# Pas_Schematic.net
KiCad netlist of a schematic drawn in Altium Designer
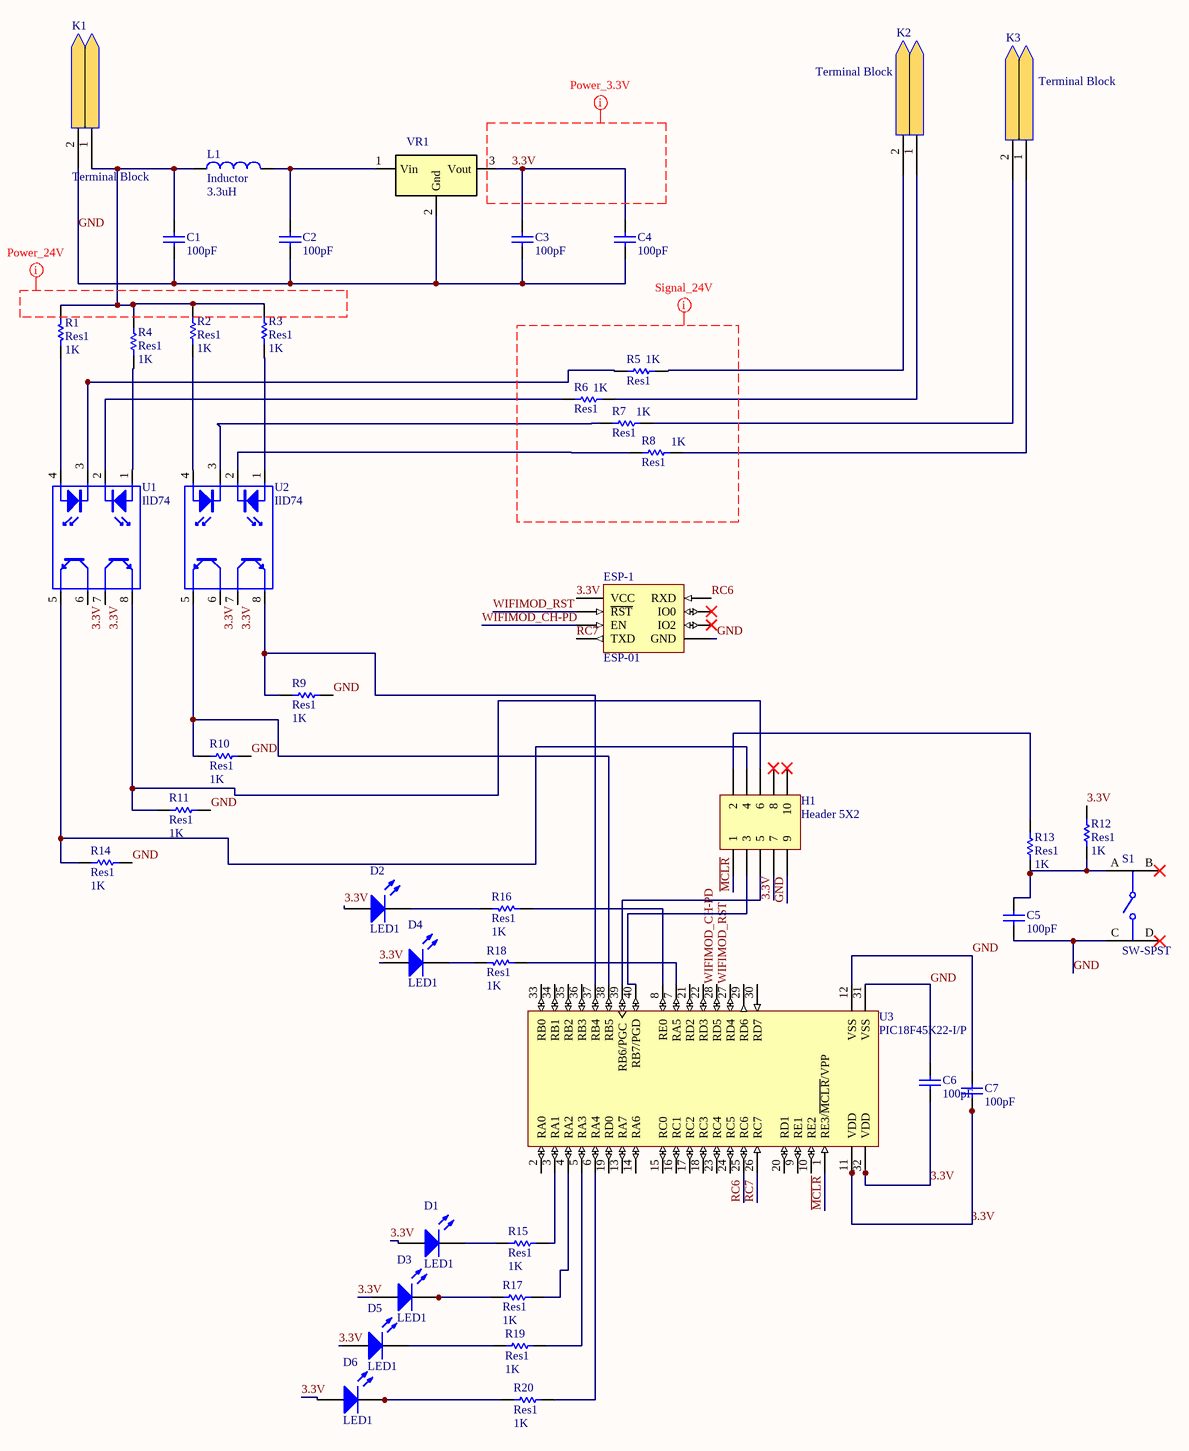
[diagram p0: Pas_Schematic.SchDoc]

(export (version "E")
  (design (tool "Eeschema 10.0.6"))
  (components
    (comp (ref "C1")
      (value "100pF")
      (footprint "RADIAL_0.2")
      (description "Capacitor")
      (fields (field (name "PUBLISHER") "Altium Limited"))
      (libsource (lib "Patient Alarm System Altium Integrated Library of Components") (part "Capacitor"))
    )
    (comp (ref "C2")
      (value "100pF")
      (footprint "RADIAL_0.2")
      (description "Capacitor")
      (fields (field (name "PUBLISHER") "Altium Limited"))
      (libsource (lib "Patient Alarm System Altium Integrated Library of Components") (part "Capacitor"))
    )
    (comp (ref "C3")
      (value "100pF")
      (footprint "RADIAL_0.2")
      (description "Capacitor")
      (fields (field (name "PUBLISHER") "Altium Limited"))
      (libsource (lib "Patient Alarm System Altium Integrated Library of Components") (part "Capacitor"))
    )
    (comp (ref "C4")
      (value "100pF")
      (footprint "RADIAL_0.2")
      (description "Capacitor")
      (fields (field (name "PUBLISHER") "Altium Limited"))
      (libsource (lib "Patient Alarm System Altium Integrated Library of Components") (part "Capacitor"))
    )
    (comp (ref "C5")
      (value "100pF")
      (footprint "RADIAL_0.2")
      (description "Capacitor")
      (fields (field (name "PUBLISHER") "Altium Limited"))
      (libsource (lib "Patient Alarm System Altium Integrated Library of Components") (part "Capacitor"))
    )
    (comp (ref "C6")
      (value "100pF")
      (footprint "RADIAL_0.2")
      (description "Capacitor")
      (fields (field (name "PUBLISHER") "Altium Limited"))
      (libsource (lib "Patient Alarm System Altium Integrated Library of Components") (part "Capacitor"))
    )
    (comp (ref "C7")
      (value "100pF")
      (footprint "RADIAL_0.2")
      (description "Capacitor")
      (fields (field (name "PUBLISHER") "Altium Limited"))
      (libsource (lib "Patient Alarm System Altium Integrated Library of Components") (part "Capacitor"))
    )
    (comp (ref "D1")
      (value "LED1")
      (footprint "RADIAL_0.2")
      (description "Typical RED GaAs LED")
      (fields (field (name "PUBLISHER") "Altium Limited"))
      (libsource (lib "Patient Alarm System Altium Integrated Library of Components") (part "LED1"))
    )
    (comp (ref "D2")
      (value "LED1")
      (footprint "RADIAL_0.2")
      (description "Typical RED GaAs LED")
      (fields (field (name "PUBLISHER") "Altium Limited"))
      (libsource (lib "Patient Alarm System Altium Integrated Library of Components") (part "LED1"))
    )
    (comp (ref "D3")
      (value "LED1")
      (footprint "RADIAL_0.2")
      (description "Typical RED GaAs LED")
      (fields (field (name "PUBLISHER") "Altium Limited"))
      (libsource (lib "Patient Alarm System Altium Integrated Library of Components") (part "LED1"))
    )
    (comp (ref "D4")
      (value "LED1")
      (footprint "RADIAL_0.2")
      (description "Typical RED GaAs LED")
      (fields (field (name "PUBLISHER") "Altium Limited"))
      (libsource (lib "Patient Alarm System Altium Integrated Library of Components") (part "LED1"))
    )
    (comp (ref "D5")
      (value "LED1")
      (footprint "RADIAL_0.2")
      (description "Typical RED GaAs LED")
      (fields (field (name "PUBLISHER") "Altium Limited"))
      (libsource (lib "Patient Alarm System Altium Integrated Library of Components") (part "LED1"))
    )
    (comp (ref "D6")
      (value "LED1")
      (footprint "RADIAL_0.2")
      (description "Typical RED GaAs LED")
      (fields (field (name "PUBLISHER") "Altium Limited"))
      (libsource (lib "Patient Alarm System Altium Integrated Library of Components") (part "LED1"))
    )
    (comp (ref "ESP-1")
      (value "ESP-01")
      (footprint "ESP-01")
      (description "802.11b/g/n Wi-Fi SOC module")
      (fields (field (name "PUBLISHER") "Altium Limited"))
      (libsource (lib "Patient Alarm System Altium Integrated Library of Components") (part "ESP-01"))
    )
    (comp (ref "H1")
      (value "Header 5X2")
      (footprint "HDR2X5")
      (description "Header, 5-Pin, Dual row")
      (fields (field (name "PUBLISHER") "Altium Limited"))
      (libsource (lib "Miscellaneous Connectors") (part "Header 5X2"))
    )
    (comp (ref "K1")
      (value "Terminal Block")
      (footprint "Altech MV-252")
      (libsource (lib "Schematic Components") (part "Terminal Block"))
    )
    (comp (ref "K2")
      (value "Terminal Block")
      (footprint "Altech MV-252")
      (libsource (lib "Schematic Components") (part "Terminal Block"))
    )
    (comp (ref "K3")
      (value "Terminal Block")
      (footprint "Altech MV-252")
      (libsource (lib "Schematic Components") (part "Terminal Block"))
    )
    (comp (ref "L1")
      (value "Inductor")
      (footprint "RADIAL_3.5")
      (fields (field (name "ALTIUM_VALUE") "3.3uH") (field (name "PUBLISHER") "Altium Limited"))
      (libsource (lib "Patient Alarm System Altium Integrated Library of Components") (part "Inductor"))
    )
    (comp (ref "R1")
      (value "Res1")
      (footprint "AXIAL-0.3")
      (description "Resistor")
      (fields (field (name "ALTIUM_VALUE") "1K") (field (name "PUBLISHER") "Altium Limited"))
      (libsource (lib "Patient Alarm System Altium Integrated Library of Components") (part "Res1"))
    )
    (comp (ref "R2")
      (value "Res1")
      (footprint "AXIAL-0.3")
      (description "Resistor")
      (fields (field (name "ALTIUM_VALUE") "1K") (field (name "PUBLISHER") "Altium Limited"))
      (libsource (lib "Patient Alarm System Altium Integrated Library of Components") (part "Res1"))
    )
    (comp (ref "R3")
      (value "Res1")
      (footprint "AXIAL-0.3")
      (description "Resistor")
      (fields (field (name "ALTIUM_VALUE") "1K") (field (name "PUBLISHER") "Altium Limited"))
      (libsource (lib "Patient Alarm System Altium Integrated Library of Components") (part "Res1"))
    )
    (comp (ref "R4")
      (value "Res1")
      (footprint "AXIAL-0.3")
      (description "Resistor")
      (fields (field (name "ALTIUM_VALUE") "1K") (field (name "PUBLISHER") "Altium Limited"))
      (libsource (lib "Patient Alarm System Altium Integrated Library of Components") (part "Res1"))
    )
    (comp (ref "R5")
      (value "Res1")
      (footprint "AXIAL-0.3")
      (description "Resistor")
      (fields (field (name "ALTIUM_VALUE") "1K") (field (name "PUBLISHER") "Altium Limited"))
      (libsource (lib "Patient Alarm System Altium Integrated Library of Components") (part "Res1"))
    )
    (comp (ref "R6")
      (value "Res1")
      (footprint "AXIAL-0.3")
      (description "Resistor")
      (fields (field (name "ALTIUM_VALUE") "1K") (field (name "PUBLISHER") "Altium Limited"))
      (libsource (lib "Patient Alarm System Altium Integrated Library of Components") (part "Res1"))
    )
    (comp (ref "R7")
      (value "Res1")
      (footprint "AXIAL-0.3")
      (description "Resistor")
      (fields (field (name "ALTIUM_VALUE") "1K") (field (name "PUBLISHER") "Altium Limited"))
      (libsource (lib "Patient Alarm System Altium Integrated Library of Components") (part "Res1"))
    )
    (comp (ref "R8")
      (value "Res1")
      (footprint "AXIAL-0.3")
      (description "Resistor")
      (fields (field (name "ALTIUM_VALUE") "1K") (field (name "PUBLISHER") "Altium Limited"))
      (libsource (lib "Patient Alarm System Altium Integrated Library of Components") (part "Res1"))
    )
    (comp (ref "R9")
      (value "Res1")
      (footprint "AXIAL-0.3")
      (description "Resistor")
      (fields (field (name "ALTIUM_VALUE") "1K") (field (name "PUBLISHER") "Altium Limited"))
      (libsource (lib "Patient Alarm System Altium Integrated Library of Components") (part "Res1"))
    )
    (comp (ref "R10")
      (value "Res1")
      (footprint "AXIAL-0.3")
      (description "Resistor")
      (fields (field (name "ALTIUM_VALUE") "1K") (field (name "PUBLISHER") "Altium Limited"))
      (libsource (lib "Patient Alarm System Altium Integrated Library of Components") (part "Res1"))
    )
    (comp (ref "R11")
      (value "Res1")
      (footprint "AXIAL-0.3")
      (description "Resistor")
      (fields (field (name "ALTIUM_VALUE") "1K") (field (name "PUBLISHER") "Altium Limited"))
      (libsource (lib "Patient Alarm System Altium Integrated Library of Components") (part "Res1"))
    )
    (comp (ref "R12")
      (value "Res1")
      (footprint "AXIAL-0.3")
      (description "Resistor")
      (fields (field (name "ALTIUM_VALUE") "1K") (field (name "PUBLISHER") "Altium Limited"))
      (libsource (lib "Patient Alarm System Altium Integrated Library of Components") (part "Res1"))
    )
    (comp (ref "R13")
      (value "Res1")
      (footprint "AXIAL-0.3")
      (description "Resistor")
      (fields (field (name "ALTIUM_VALUE") "1K") (field (name "PUBLISHER") "Altium Limited"))
      (libsource (lib "Patient Alarm System Altium Integrated Library of Components") (part "Res1"))
    )
    (comp (ref "R14")
      (value "Res1")
      (footprint "AXIAL-0.3")
      (description "Resistor")
      (fields (field (name "ALTIUM_VALUE") "1K") (field (name "PUBLISHER") "Altium Limited"))
      (libsource (lib "Patient Alarm System Altium Integrated Library of Components") (part "Res1"))
    )
    (comp (ref "R15")
      (value "Res1")
      (footprint "AXIAL-0.3")
      (description "Resistor")
      (fields (field (name "ALTIUM_VALUE") "1K") (field (name "PUBLISHER") "Altium Limited"))
      (libsource (lib "Patient Alarm System Altium Integrated Library of Components") (part "Res1"))
    )
    (comp (ref "R16")
      (value "Res1")
      (footprint "AXIAL-0.3")
      (description "Resistor")
      (fields (field (name "ALTIUM_VALUE") "1K") (field (name "PUBLISHER") "Altium Limited"))
      (libsource (lib "Patient Alarm System Altium Integrated Library of Components") (part "Res1"))
    )
    (comp (ref "R17")
      (value "Res1")
      (footprint "AXIAL-0.3")
      (description "Resistor")
      (fields (field (name "ALTIUM_VALUE") "1K") (field (name "PUBLISHER") "Altium Limited"))
      (libsource (lib "Patient Alarm System Altium Integrated Library of Components") (part "Res1"))
    )
    (comp (ref "R18")
      (value "Res1")
      (footprint "AXIAL-0.3")
      (description "Resistor")
      (fields (field (name "ALTIUM_VALUE") "1K") (field (name "PUBLISHER") "Altium Limited"))
      (libsource (lib "Patient Alarm System Altium Integrated Library of Components") (part "Res1"))
    )
    (comp (ref "R19")
      (value "Res1")
      (footprint "AXIAL-0.3")
      (description "Resistor")
      (fields (field (name "ALTIUM_VALUE") "1K") (field (name "PUBLISHER") "Altium Limited"))
      (libsource (lib "Patient Alarm System Altium Integrated Library of Components") (part "Res1"))
    )
    (comp (ref "R20")
      (value "Res1")
      (footprint "AXIAL-0.3")
      (description "Resistor")
      (fields (field (name "ALTIUM_VALUE") "1K") (field (name "PUBLISHER") "Altium Limited"))
      (libsource (lib "Patient Alarm System Altium Integrated Library of Components") (part "Res1"))
    )
    (comp (ref "S1")
      (value "SW-SPST")
      (footprint "SW-SPST-1")
      (description "4-pin Single-Pole, Single-Throw Switch")
      (fields (field (name "PUBLISHER") "Altium Limited"))
      (libsource (lib "Patient Alarm System Altium Integrated Library of Components") (part "SW-SPST"))
    )
    (comp (ref "U1")
      (value "IlD74")
      (footprint "DIP-8")
      (description "8-pin Dual Optocoupler with NPN Transistor Output")
      (fields (field (name "PUBLISHER") "Altium Limited"))
      (libsource (lib "Patient Alarm System Altium Integrated Library of Components") (part "IlD74"))
    )
    (comp (ref "U2")
      (value "IlD74")
      (footprint "DIP-8")
      (description "8-pin Dual Optocoupler with NPN Transistor Output")
      (fields (field (name "PUBLISHER") "Altium Limited"))
      (libsource (lib "Patient Alarm System Altium Integrated Library of Components") (part "IlD74"))
    )
    (comp (ref "U3")
      (value "PIC18F45K22-I/P")
      (footprint "MCHP-PDIP-P40")
      (fields (field (name "MANUFACTURER") "Microchip"))
      (libsource (lib "Patient Alarm System Altium Integrated Library of Components") (part "PIC18F45K22-I/P"))
    )
    (comp (ref "VR1")
      (value "REG")
      (footprint "SIP3")
      (description "Non-Isolated DC/DC Converters 0.5A DC/DC REG 4.75-34Vin 3.3Vout")
      (libsource (lib "Patient Alarm System Altium Integrated Library of Components") (part "R-783.3-0.5"))
    )
  )
  (nets
    (net (code "1") (name "/3.3V") (class "Default")
      (node (ref "C3") (pin "1") (pinfunction "1_1") (pintype "passive"))
      (node (ref "C4") (pin "1") (pinfunction "1_1") (pintype "passive"))
      (node (ref "C6") (pin "1") (pinfunction "1_1") (pintype "passive"))
      (node (ref "C7") (pin "1") (pinfunction "1_1") (pintype "passive"))
      (node (ref "D1") (pin "1") (pinfunction "A_1") (pintype "passive"))
      (node (ref "D2") (pin "1") (pinfunction "A_1") (pintype "passive"))
      (node (ref "D3") (pin "1") (pinfunction "A_1") (pintype "passive"))
      (node (ref "D4") (pin "1") (pinfunction "A_1") (pintype "passive"))
      (node (ref "D5") (pin "1") (pinfunction "A_1") (pintype "passive"))
      (node (ref "D6") (pin "1") (pinfunction "A_1") (pintype "passive"))
      (node (ref "ESP-1") (pin "8") (pinfunction "VCC_8") (pintype "power_in"))
      (node (ref "H1") (pin "7") (pinfunction "7_7") (pintype "passive"))
      (node (ref "R12") (pin "2") (pinfunction "2_2") (pintype "passive"))
      (node (ref "U1") (pin "6") (pinfunction "C_6") (pintype "passive"))
      (node (ref "U1") (pin "7") (pinfunction "C_7") (pintype "passive"))
      (node (ref "U2") (pin "6") (pinfunction "C_6") (pintype "passive"))
      (node (ref "U2") (pin "7") (pinfunction "C_7") (pintype "passive"))
      (node (ref "U3") (pin "11") (pinfunction "VDD_11") (pintype "power_in"))
      (node (ref "U3") (pin "32") (pinfunction "VDD_32") (pintype "power_in"))
      (node (ref "VR1") (pin "3") (pinfunction "Vout_3") (pintype "power_in"))
    )
    (net (code "2") (name "/GND") (class "Default")
      (node (ref "C1") (pin "2") (pinfunction "2_2") (pintype "passive"))
      (node (ref "C2") (pin "2") (pinfunction "2_2") (pintype "passive"))
      (node (ref "C3") (pin "2") (pinfunction "2_2") (pintype "passive"))
      (node (ref "C4") (pin "2") (pinfunction "2_2") (pintype "passive"))
      (node (ref "C5") (pin "2") (pinfunction "2_2") (pintype "passive"))
      (node (ref "C6") (pin "2") (pinfunction "2_2") (pintype "passive"))
      (node (ref "C7") (pin "2") (pinfunction "2_2") (pintype "passive"))
      (node (ref "ESP-1") (pin "1") (pinfunction "GND_1") (pintype "power_in"))
      (node (ref "H1") (pin "9") (pinfunction "9_9") (pintype "passive"))
      (node (ref "K1") (pin "2") (pinfunction "Cable_2_2") (pintype "passive"))
      (node (ref "R10") (pin "1") (pinfunction "1_1") (pintype "passive"))
      (node (ref "R11") (pin "1") (pinfunction "1_1") (pintype "passive"))
      (node (ref "R14") (pin "1") (pinfunction "1_1") (pintype "passive"))
      (node (ref "R9") (pin "1") (pinfunction "1_1") (pintype "passive"))
      (node (ref "S1") (pin "C") (pinfunction "NO_C") (pintype "passive"))
      (node (ref "U3") (pin "12") (pinfunction "VSS_12") (pintype "power_in"))
      (node (ref "U3") (pin "31") (pinfunction "VSS_31") (pintype "power_in"))
      (node (ref "VR1") (pin "2") (pinfunction "Gnd_2") (pintype "power_in"))
    )
    (net (code "3") (name "/RC6") (class "Default")
      (node (ref "ESP-1") (pin "4") (pinfunction "RXD_4") (pintype "input"))
      (node (ref "U3") (pin "25") (pinfunction "RC6_25") (pintype "bidirectional"))
    )
    (net (code "4") (name "/RC7") (class "Default")
      (node (ref "ESP-1") (pin "5") (pinfunction "TXD_5") (pintype "output"))
      (node (ref "U3") (pin "26") (pinfunction "RC7_26") (pintype "input"))
    )
    (net (code "5") (name "/WIFIMOD_CH-PD") (class "Default")
      (node (ref "ESP-1") (pin "6") (pinfunction "EN_6") (pintype "input"))
      (node (ref "U3") (pin "28") (pinfunction "RD5_28") (pintype "bidirectional"))
    )
    (net (code "6") (name "/WIFIMOD_RST") (class "Default")
      (node (ref "ESP-1") (pin "7") (pinfunction "~{RST}_7") (pintype "input"))
      (node (ref "U3") (pin "27") (pinfunction "RD4_27") (pintype "bidirectional"))
    )
    (net (code "7") (name "/~{MCLR}") (class "Default")
      (node (ref "H1") (pin "1") (pinfunction "1_1") (pintype "power_in"))
      (node (ref "U3") (pin "1") (pinfunction "RE3/~{MCLR}/VPP_1") (pintype "input"))
    )
    (net (code "8") (name "Net-(C5-Pad1)") (class "Default")
      (node (ref "C5") (pin "1") (pinfunction "1_1") (pintype "passive"))
      (node (ref "R12") (pin "1") (pinfunction "1_1") (pintype "passive"))
      (node (ref "R13") (pin "1") (pinfunction "1_1") (pintype "passive"))
      (node (ref "S1") (pin "A") (pinfunction "COMMON_A") (pintype "passive"))
    )
    (net (code "9") (name "Net-(D1-K)") (class "Default")
      (node (ref "D1") (pin "2") (pinfunction "K_2") (pintype "passive"))
      (node (ref "R15") (pin "2") (pinfunction "2_2") (pintype "passive"))
    )
    (net (code "10") (name "Net-(D2-K)") (class "Default")
      (node (ref "D2") (pin "2") (pinfunction "K_2") (pintype "passive"))
      (node (ref "R16") (pin "2") (pinfunction "2_2") (pintype "passive"))
    )
    (net (code "11") (name "Net-(D3-K)") (class "Default")
      (node (ref "D3") (pin "2") (pinfunction "K_2") (pintype "passive"))
      (node (ref "R17") (pin "1") (pinfunction "1_1") (pintype "passive"))
    )
    (net (code "12") (name "Net-(D4-K)") (class "Default")
      (node (ref "D4") (pin "2") (pinfunction "K_2") (pintype "passive"))
      (node (ref "R18") (pin "2") (pinfunction "2_2") (pintype "passive"))
    )
    (net (code "13") (name "Net-(D5-K)") (class "Default")
      (node (ref "D5") (pin "2") (pinfunction "K_2") (pintype "passive"))
      (node (ref "R19") (pin "1") (pinfunction "1_1") (pintype "passive"))
    )
    (net (code "14") (name "Net-(D6-K)") (class "Default")
      (node (ref "D6") (pin "2") (pinfunction "K_2") (pintype "passive"))
      (node (ref "R20") (pin "1") (pinfunction "1_1") (pintype "passive"))
    )
    (net (code "15") (name "Net-(H1-Pad2)") (class "Default")
      (node (ref "H1") (pin "2") (pinfunction "2_2") (pintype "passive"))
      (node (ref "R13") (pin "2") (pinfunction "2_2") (pintype "passive"))
    )
    (net (code "16") (name "Net-(H1-Pad4)") (class "Default")
      (node (ref "H1") (pin "4") (pinfunction "4_4") (pintype "passive"))
      (node (ref "R14") (pin "2") (pinfunction "2_2") (pintype "passive"))
      (node (ref "U1") (pin "5") (pinfunction "E_5") (pintype "passive"))
    )
    (net (code "17") (name "Net-(H1-Pad6)") (class "Default")
      (node (ref "H1") (pin "6") (pinfunction "6_6") (pintype "passive"))
      (node (ref "R11") (pin "2") (pinfunction "2_2") (pintype "passive"))
      (node (ref "U1") (pin "8") (pinfunction "E_8") (pintype "passive"))
    )
    (net (code "18") (name "Net-(K1-Cable_1)") (class "Default")
      (node (ref "C1") (pin "1") (pinfunction "1_1") (pintype "passive"))
      (node (ref "K1") (pin "1") (pinfunction "Cable_1_1") (pintype "passive"))
      (node (ref "L1") (pin "1") (pinfunction "1_1") (pintype "passive"))
      (node (ref "R1") (pin "1") (pinfunction "1_1") (pintype "passive"))
      (node (ref "R2") (pin "2") (pinfunction "2_2") (pintype "passive"))
      (node (ref "R3") (pin "2") (pinfunction "2_2") (pintype "passive"))
      (node (ref "R4") (pin "2") (pinfunction "2_2") (pintype "passive"))
    )
    (net (code "19") (name "Net-(K2-Cable_1)") (class "Default")
      (node (ref "K2") (pin "1") (pinfunction "Cable_1_1") (pintype "passive"))
      (node (ref "R6") (pin "2") (pinfunction "2_2") (pintype "passive"))
    )
    (net (code "20") (name "Net-(K2-Cable_2)") (class "Default")
      (node (ref "K2") (pin "2") (pinfunction "Cable_2_2") (pintype "passive"))
      (node (ref "R5") (pin "2") (pinfunction "2_2") (pintype "passive"))
    )
    (net (code "21") (name "Net-(K3-Cable_1)") (class "Default")
      (node (ref "K3") (pin "1") (pinfunction "Cable_1_1") (pintype "passive"))
      (node (ref "R8") (pin "2") (pinfunction "2_2") (pintype "passive"))
    )
    (net (code "22") (name "Net-(K3-Cable_2)") (class "Default")
      (node (ref "K3") (pin "2") (pinfunction "Cable_2_2") (pintype "passive"))
      (node (ref "R7") (pin "2") (pinfunction "2_2") (pintype "passive"))
    )
    (net (code "23") (name "Net-(R1-Pad2)") (class "Default")
      (node (ref "R1") (pin "2") (pinfunction "2_2") (pintype "passive"))
      (node (ref "U1") (pin "4") (pinfunction "A_4") (pintype "passive"))
    )
    (net (code "24") (name "Net-(R2-Pad1)") (class "Default")
      (node (ref "R2") (pin "1") (pinfunction "1_1") (pintype "passive"))
      (node (ref "U2") (pin "4") (pinfunction "A_4") (pintype "passive"))
    )
    (net (code "25") (name "Net-(R3-Pad1)") (class "Default")
      (node (ref "R3") (pin "1") (pinfunction "1_1") (pintype "passive"))
      (node (ref "U2") (pin "1") (pinfunction "A_1") (pintype "passive"))
    )
    (net (code "26") (name "Net-(R4-Pad1)") (class "Default")
      (node (ref "R4") (pin "1") (pinfunction "1_1") (pintype "passive"))
      (node (ref "U1") (pin "1") (pinfunction "A_1") (pintype "passive"))
    )
    (net (code "27") (name "Net-(R5-Pad1)") (class "Default")
      (node (ref "R5") (pin "1") (pinfunction "1_1") (pintype "passive"))
      (node (ref "U1") (pin "3") (pinfunction "K_3") (pintype "passive"))
    )
    (net (code "28") (name "Net-(R6-Pad1)") (class "Default")
      (node (ref "R6") (pin "1") (pinfunction "1_1") (pintype "passive"))
      (node (ref "U1") (pin "2") (pinfunction "K_2") (pintype "passive"))
    )
    (net (code "29") (name "Net-(R7-Pad1)") (class "Default")
      (node (ref "R7") (pin "1") (pinfunction "1_1") (pintype "passive"))
      (node (ref "U2") (pin "3") (pinfunction "K_3") (pintype "passive"))
    )
    (net (code "30") (name "Net-(R8-Pad1)") (class "Default")
      (node (ref "R8") (pin "1") (pinfunction "1_1") (pintype "passive"))
      (node (ref "U2") (pin "2") (pinfunction "K_2") (pintype "passive"))
    )
    (net (code "31") (name "Net-(U3-RA1)") (class "Default")
      (node (ref "R15") (pin "1") (pinfunction "1_1") (pintype "passive"))
      (node (ref "U3") (pin "3") (pinfunction "RA1_3") (pintype "bidirectional"))
    )
    (net (code "32") (name "Net-(U3-RA2)") (class "Default")
      (node (ref "R17") (pin "2") (pinfunction "2_2") (pintype "passive"))
      (node (ref "U3") (pin "4") (pinfunction "RA2_4") (pintype "bidirectional"))
    )
    (net (code "33") (name "Net-(U3-RA3)") (class "Default")
      (node (ref "R19") (pin "2") (pinfunction "2_2") (pintype "passive"))
      (node (ref "U3") (pin "5") (pinfunction "RA3_5") (pintype "bidirectional"))
    )
    (net (code "34") (name "Net-(U3-RA4)") (class "Default")
      (node (ref "R20") (pin "2") (pinfunction "2_2") (pintype "passive"))
      (node (ref "U3") (pin "6") (pinfunction "RA4_6") (pintype "bidirectional"))
    )
    (net (code "35") (name "Net-(U3-RA5)") (class "Default")
      (node (ref "R18") (pin "1") (pinfunction "1_1") (pintype "passive"))
      (node (ref "U3") (pin "7") (pinfunction "RA5_7") (pintype "bidirectional"))
    )
    (net (code "36") (name "Net-(U3-RB4)") (class "Default")
      (node (ref "R9") (pin "2") (pinfunction "2_2") (pintype "passive"))
      (node (ref "U2") (pin "8") (pinfunction "E_8") (pintype "passive"))
      (node (ref "U3") (pin "37") (pinfunction "RB4_37") (pintype "bidirectional"))
    )
    (net (code "37") (name "Net-(U3-RB5)") (class "Default")
      (node (ref "R10") (pin "2") (pinfunction "2_2") (pintype "passive"))
      (node (ref "U2") (pin "5") (pinfunction "E_5") (pintype "passive"))
      (node (ref "U3") (pin "38") (pinfunction "RB5_38") (pintype "bidirectional"))
    )
    (net (code "38") (name "Net-(U3-RB6{slash}PGC)") (class "Default")
      (node (ref "H1") (pin "5") (pinfunction "5_5") (pintype "passive"))
      (node (ref "U3") (pin "39") (pinfunction "RB6/PGC_39") (pintype "bidirectional"))
    )
    (net (code "39") (name "Net-(U3-RB7{slash}PGD)") (class "Default")
      (node (ref "H1") (pin "3") (pinfunction "3_3") (pintype "passive"))
      (node (ref "U3") (pin "40") (pinfunction "RB7/PGD_40") (pintype "bidirectional"))
    )
    (net (code "40") (name "Net-(U3-RE0)") (class "Default")
      (node (ref "R16") (pin "1") (pinfunction "1_1") (pintype "passive"))
      (node (ref "U3") (pin "8") (pinfunction "RE0_8") (pintype "bidirectional"))
    )
    (net (code "41") (name "Net-(VR1-Vin)") (class "Default")
      (node (ref "C2") (pin "1") (pinfunction "1_1") (pintype "passive"))
      (node (ref "L1") (pin "2") (pinfunction "2_2") (pintype "passive"))
      (node (ref "VR1") (pin "1") (pinfunction "Vin_1") (pintype "power_in"))
    )
    (net (code "42") (name "unconnected-(ESP-1-IO0-Pad3)") (class "Default")
      (node (ref "ESP-1") (pin "3") (pinfunction "IO0_3") (pintype "bidirectional+no_connect"))
    )
    (net (code "43") (name "unconnected-(ESP-1-IO2-Pad2)") (class "Default")
      (node (ref "ESP-1") (pin "2") (pinfunction "IO2_2") (pintype "bidirectional+no_connect"))
    )
    (net (code "44") (name "unconnected-(H1-Pad8)") (class "Default")
      (node (ref "H1") (pin "8") (pinfunction "8_8") (pintype "passive+no_connect"))
    )
    (net (code "45") (name "unconnected-(H1-Pad10)") (class "Default")
      (node (ref "H1") (pin "10") (pinfunction "10_10") (pintype "passive+no_connect"))
    )
    (net (code "46") (name "unconnected-(S1-COMMON-PadB)") (class "Default")
      (node (ref "S1") (pin "B") (pinfunction "COMMON_B") (pintype "passive+no_connect"))
    )
    (net (code "47") (name "unconnected-(S1-NO-PadD)") (class "Default")
      (node (ref "S1") (pin "D") (pinfunction "NO_D") (pintype "passive+no_connect"))
    )
    (net (code "48") (name "unconnected-(U3-RA0-Pad2)") (class "Default")
      (node (ref "U3") (pin "2") (pinfunction "RA0_2") (pintype "bidirectional"))
    )
    (net (code "49") (name "unconnected-(U3-RA6-Pad14)") (class "Default")
      (node (ref "U3") (pin "14") (pinfunction "RA6_14") (pintype "bidirectional"))
    )
    (net (code "50") (name "unconnected-(U3-RA7-Pad13)") (class "Default")
      (node (ref "U3") (pin "13") (pinfunction "RA7_13") (pintype "bidirectional"))
    )
    (net (code "51") (name "unconnected-(U3-RB0-Pad33)") (class "Default")
      (node (ref "U3") (pin "33") (pinfunction "RB0_33") (pintype "bidirectional"))
    )
    (net (code "52") (name "unconnected-(U3-RB1-Pad34)") (class "Default")
      (node (ref "U3") (pin "34") (pinfunction "RB1_34") (pintype "bidirectional"))
    )
    (net (code "53") (name "unconnected-(U3-RB2-Pad35)") (class "Default")
      (node (ref "U3") (pin "35") (pinfunction "RB2_35") (pintype "bidirectional"))
    )
    (net (code "54") (name "unconnected-(U3-RB3-Pad36)") (class "Default")
      (node (ref "U3") (pin "36") (pinfunction "RB3_36") (pintype "bidirectional"))
    )
    (net (code "55") (name "unconnected-(U3-RC0-Pad15)") (class "Default")
      (node (ref "U3") (pin "15") (pinfunction "RC0_15") (pintype "bidirectional"))
    )
    (net (code "56") (name "unconnected-(U3-RC1-Pad16)") (class "Default")
      (node (ref "U3") (pin "16") (pinfunction "RC1_16") (pintype "bidirectional"))
    )
    (net (code "57") (name "unconnected-(U3-RC2-Pad17)") (class "Default")
      (node (ref "U3") (pin "17") (pinfunction "RC2_17") (pintype "bidirectional"))
    )
    (net (code "58") (name "unconnected-(U3-RC3-Pad18)") (class "Default")
      (node (ref "U3") (pin "18") (pinfunction "RC3_18") (pintype "bidirectional"))
    )
    (net (code "59") (name "unconnected-(U3-RC4-Pad23)") (class "Default")
      (node (ref "U3") (pin "23") (pinfunction "RC4_23") (pintype "bidirectional"))
    )
    (net (code "60") (name "unconnected-(U3-RC5-Pad24)") (class "Default")
      (node (ref "U3") (pin "24") (pinfunction "RC5_24") (pintype "bidirectional"))
    )
    (net (code "61") (name "unconnected-(U3-RD0-Pad19)") (class "Default")
      (node (ref "U3") (pin "19") (pinfunction "RD0_19") (pintype "bidirectional"))
    )
    (net (code "62") (name "unconnected-(U3-RD1-Pad20)") (class "Default")
      (node (ref "U3") (pin "20") (pinfunction "RD1_20") (pintype "bidirectional"))
    )
    (net (code "63") (name "unconnected-(U3-RD2-Pad21)") (class "Default")
      (node (ref "U3") (pin "21") (pinfunction "RD2_21") (pintype "bidirectional"))
    )
    (net (code "64") (name "unconnected-(U3-RD3-Pad22)") (class "Default")
      (node (ref "U3") (pin "22") (pinfunction "RD3_22") (pintype "bidirectional"))
    )
    (net (code "65") (name "unconnected-(U3-RD6-Pad29)") (class "Default")
      (node (ref "U3") (pin "29") (pinfunction "RD6_29") (pintype "output"))
    )
    (net (code "66") (name "unconnected-(U3-RD7-Pad30)") (class "Default")
      (node (ref "U3") (pin "30") (pinfunction "RD7_30") (pintype "input"))
    )
    (net (code "67") (name "unconnected-(U3-RE1-Pad9)") (class "Default")
      (node (ref "U3") (pin "9") (pinfunction "RE1_9") (pintype "bidirectional"))
    )
    (net (code "68") (name "unconnected-(U3-RE2-Pad10)") (class "Default")
      (node (ref "U3") (pin "10") (pinfunction "RE2_10") (pintype "bidirectional"))
    )
  )
)
